# 4.net
KiCad netlist of a schematic drawn in EAGLE
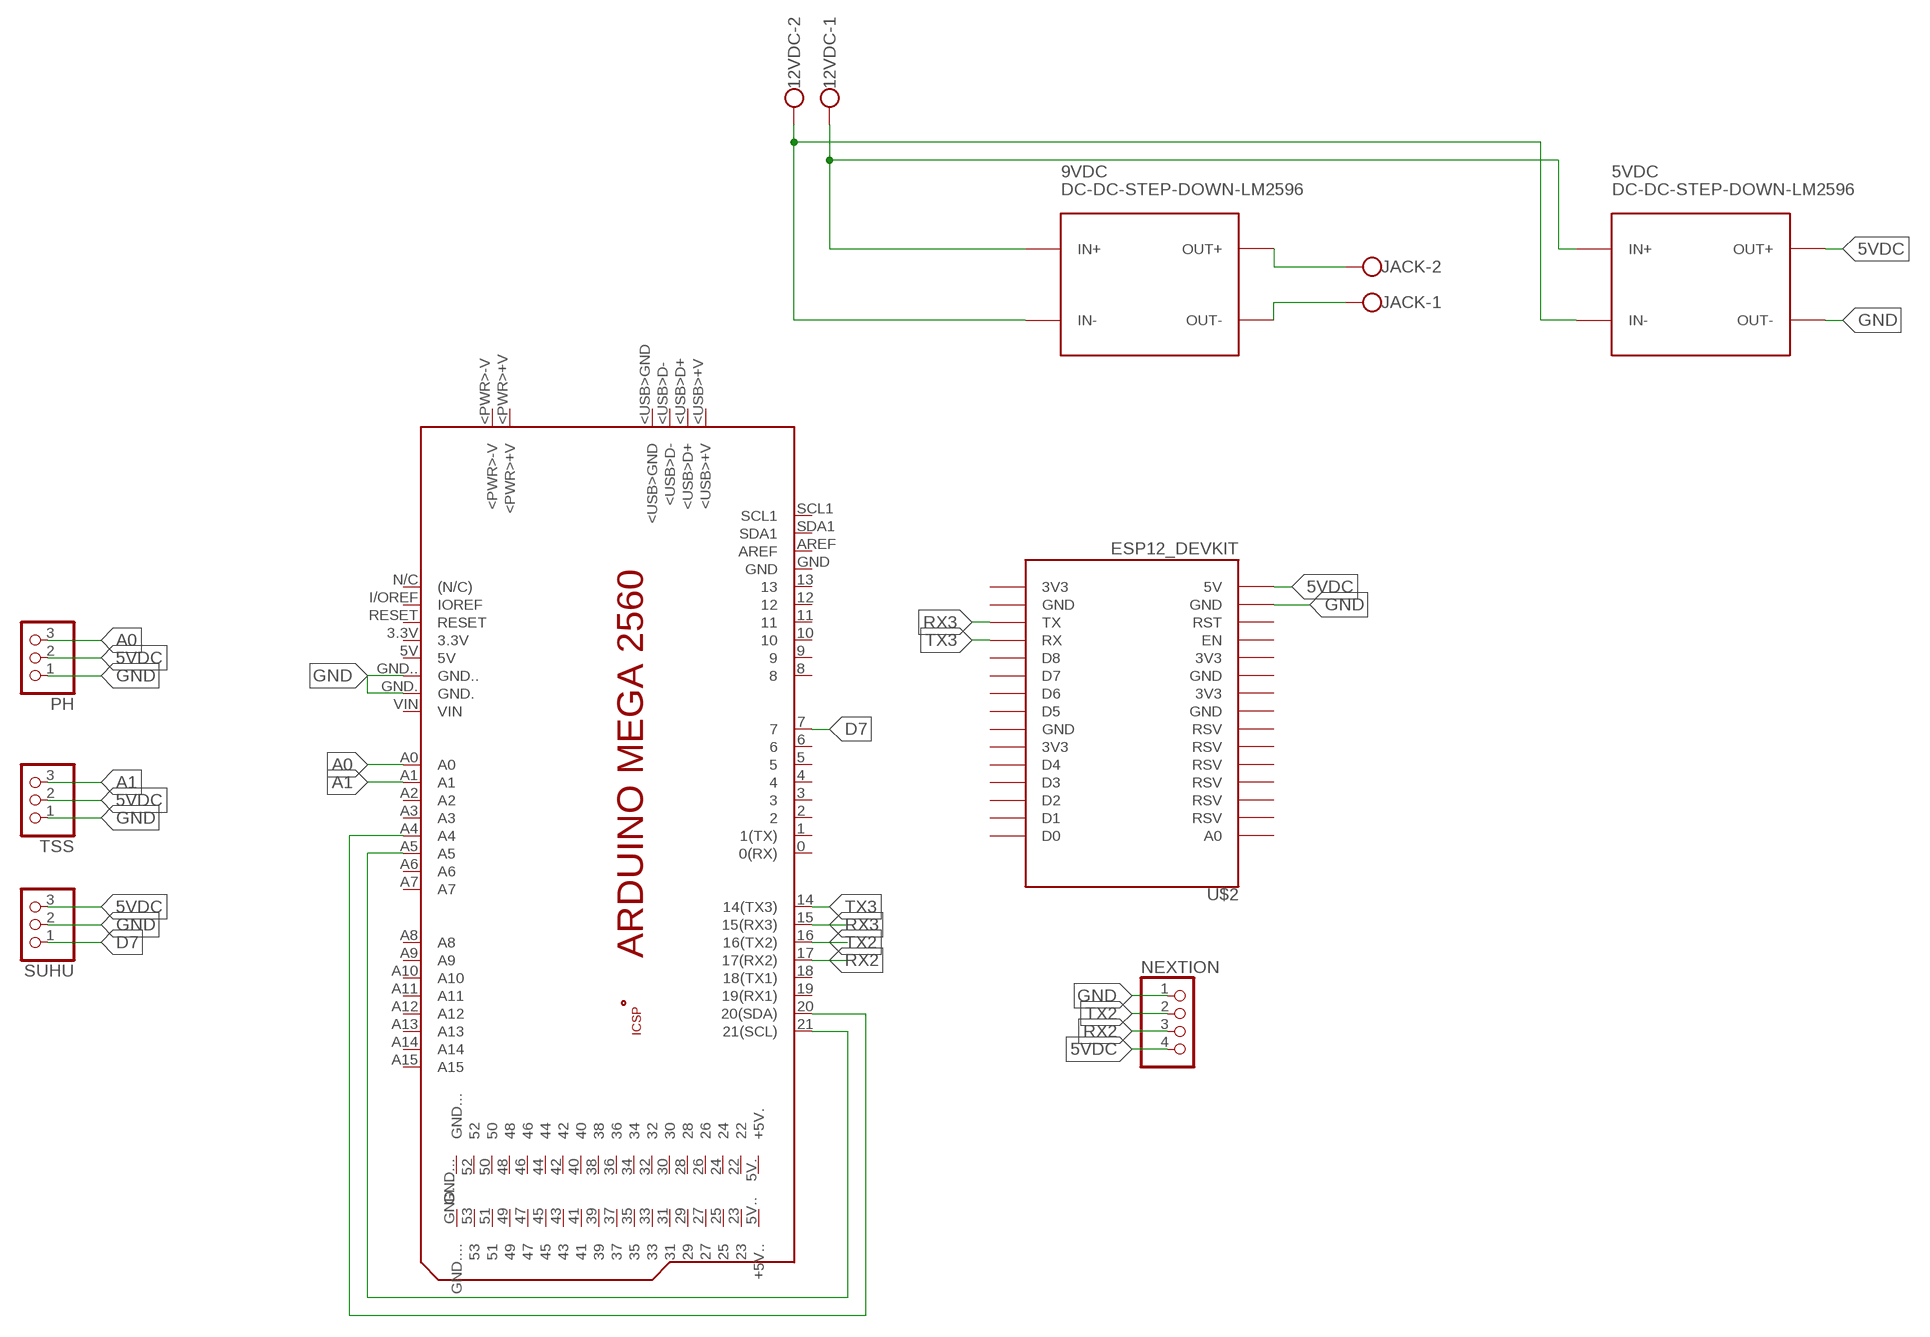
[diagram p0: schematic, sheet 1]

(export (version "E")
  (design (tool "Eeschema 10.0.6"))
  (components
    (comp (ref "5VDC")
      (value "DC-DC-STEP-DOWN-LM2596")
      (footprint "eagle-import:DC-DC-STEP-DOWN-LM2596")
      (libsource (lib "eagle-import") (part "DC-DC-STEP-DOWN-LM2596"))
    )
    (comp (ref "9VDC")
      (value "DC-DC-STEP-DOWN-LM2596")
      (footprint "eagle-import:DC-DC-STEP-DOWN-LM2596")
      (libsource (lib "eagle-import") (part "DC-DC-STEP-DOWN-LM2596"))
    )
    (comp (ref "12VDC")
      (value "W237-102")
      (footprint "eagle-import:W237-102")
      (fields (field (name "MPN") "237-102"))
      (libsource (lib "eagle-import") (part "W237-102"))
    )
    (comp (ref "JACK")
      (value "W237-102")
      (footprint "eagle-import:W237-102")
      (fields (field (name "MPN") "237-102"))
      (libsource (lib "eagle-import") (part "W237-102"))
    )
    (comp (ref "NEXTION")
      (value "PINHD-1X4")
      (footprint "eagle-import:1X04")
      (libsource (lib "eagle-import") (part "PINHD-1X4"))
    )
    (comp (ref "PCB1")
      (value "ARDUINO_MEGA2560")
      (footprint "eagle-import:ARDUINO_MEGA2560")
      (libsource (lib "eagle-import") (part "ARDUINO_MEGA2560"))
    )
    (comp (ref "PH")
      (value "PINHD-1X3")
      (footprint "eagle-import:1X03")
      (libsource (lib "eagle-import") (part "PINHD-1X3"))
    )
    (comp (ref "SUHU")
      (value "PINHD-1X3")
      (footprint "eagle-import:1X03")
      (libsource (lib "eagle-import") (part "PINHD-1X3"))
    )
    (comp (ref "TSS")
      (value "PINHD-1X3")
      (footprint "eagle-import:1X03")
      (libsource (lib "eagle-import") (part "PINHD-1X3"))
    )
    (comp (ref "U$2")
      (value "ESP12_DEVKIT")
      (footprint "eagle-import:ESP12_DEVKIT")
      (libsource (lib "eagle-import") (part "ESP12_DEVKIT"))
    )
  )
  (nets
    (net (code "1") (name "5VDC") (class "Default")
      (node (ref "5VDC") (pin "OUT+") (pinfunction "OUT+_OUT+") (pintype "bidirectional"))
      (node (ref "NEXTION") (pin "4") (pinfunction "4_4") (pintype "passive"))
      (node (ref "PH") (pin "2") (pinfunction "2_2") (pintype "passive"))
      (node (ref "SUHU") (pin "3") (pinfunction "3_3") (pintype "passive"))
      (node (ref "TSS") (pin "2") (pinfunction "2_2") (pintype "passive"))
      (node (ref "U$2") (pin "5V") (pinfunction "5V_5V") (pintype "bidirectional"))
    )
    (net (code "2") (name "A0") (class "Default")
      (node (ref "PCB1") (pin "A0") (pinfunction "A0_A0") (pintype "bidirectional"))
      (node (ref "PH") (pin "3") (pinfunction "3_3") (pintype "passive"))
    )
    (net (code "3") (name "A1") (class "Default")
      (node (ref "PCB1") (pin "A1") (pinfunction "A1_A1") (pintype "bidirectional"))
      (node (ref "TSS") (pin "3") (pinfunction "3_3") (pintype "passive"))
    )
    (net (code "4") (name "D7") (class "Default")
      (node (ref "PCB1") (pin "7") (pinfunction "7_7") (pintype "bidirectional"))
      (node (ref "SUHU") (pin "1") (pinfunction "1_1") (pintype "passive"))
    )
    (net (code "5") (name "GND") (class "Default")
      (node (ref "5VDC") (pin "OUT-") (pinfunction "OUT-_OUT-") (pintype "bidirectional"))
      (node (ref "NEXTION") (pin "1") (pinfunction "1_1") (pintype "passive"))
      (node (ref "PCB1") (pin "GND.") (pinfunction "GND._GND.") (pintype "bidirectional"))
      (node (ref "PCB1") (pin "GND..") (pinfunction "GND.._GND..") (pintype "bidirectional"))
      (node (ref "PH") (pin "1") (pinfunction "1_1") (pintype "passive"))
      (node (ref "SUHU") (pin "2") (pinfunction "2_2") (pintype "passive"))
      (node (ref "TSS") (pin "1") (pinfunction "1_1") (pintype "passive"))
      (node (ref "U$2") (pin "GND@1") (pinfunction "GND_GND@1") (pintype "bidirectional"))
    )
    (net (code "6") (name "Net-(12VDCA-KL)") (class "Default")
      (node (ref "12VDC") (pin "1") (pinfunction "KL_1") (pintype "passive"))
      (node (ref "5VDC") (pin "IN+") (pinfunction "IN+_IN+") (pintype "bidirectional"))
      (node (ref "9VDC") (pin "IN+") (pinfunction "IN+_IN+") (pintype "bidirectional"))
    )
    (net (code "7") (name "Net-(12VDCB-KL)") (class "Default")
      (node (ref "12VDC") (pin "2") (pinfunction "KL_2") (pintype "passive"))
      (node (ref "5VDC") (pin "IN-") (pinfunction "IN-_IN-") (pintype "bidirectional"))
      (node (ref "9VDC") (pin "IN-") (pinfunction "IN-_IN-") (pintype "bidirectional"))
    )
    (net (code "8") (name "Net-(JACKA-KL)") (class "Default")
      (node (ref "9VDC") (pin "OUT-") (pinfunction "OUT-_OUT-") (pintype "bidirectional"))
      (node (ref "JACK") (pin "1") (pinfunction "KL_1") (pintype "passive"))
    )
    (net (code "9") (name "Net-(JACKB-KL)") (class "Default")
      (node (ref "9VDC") (pin "OUT+") (pinfunction "OUT+_OUT+") (pintype "bidirectional"))
      (node (ref "JACK") (pin "2") (pinfunction "KL_2") (pintype "passive"))
    )
    (net (code "10") (name "Net-(PCB1-20(SDA))") (class "Default")
      (node (ref "PCB1") (pin "20") (pinfunction "20(SDA)_20") (pintype "bidirectional"))
      (node (ref "PCB1") (pin "A4") (pinfunction "A4_A4") (pintype "bidirectional"))
    )
    (net (code "11") (name "Net-(PCB1-21(SCL))") (class "Default")
      (node (ref "PCB1") (pin "21") (pinfunction "21(SCL)_21") (pintype "bidirectional"))
      (node (ref "PCB1") (pin "A5") (pinfunction "A5_A5") (pintype "bidirectional"))
    )
    (net (code "12") (name "RX2") (class "Default")
      (node (ref "NEXTION") (pin "3") (pinfunction "3_3") (pintype "passive"))
      (node (ref "PCB1") (pin "17") (pinfunction "17(RX2)_17") (pintype "bidirectional"))
    )
    (net (code "13") (name "RX3") (class "Default")
      (node (ref "PCB1") (pin "15") (pinfunction "15(RX3)_15") (pintype "bidirectional"))
      (node (ref "U$2") (pin "TX") (pinfunction "TX_TX") (pintype "bidirectional"))
    )
    (net (code "14") (name "TX2") (class "Default")
      (node (ref "NEXTION") (pin "2") (pinfunction "2_2") (pintype "passive"))
      (node (ref "PCB1") (pin "16") (pinfunction "16(TX2)_16") (pintype "bidirectional"))
    )
    (net (code "15") (name "TX3") (class "Default")
      (node (ref "PCB1") (pin "14") (pinfunction "14(TX3)_14") (pintype "bidirectional"))
      (node (ref "U$2") (pin "RX") (pinfunction "RX_RX") (pintype "bidirectional"))
    )
    (net (code "16") (name "unconnected-(PCB1-(N{slash}C)-PadN{slash}C)") (class "Default")
      (node (ref "PCB1") (pin "N/C") (pinfunction "(N/C)_N/C") (pintype "bidirectional"))
    )
    (net (code "17") (name "unconnected-(PCB1-+5V.-Pad5V.)") (class "Default")
      (node (ref "PCB1") (pin "5V.") (pinfunction "+5V._5V.") (pintype "bidirectional"))
    )
    (net (code "18") (name "unconnected-(PCB1-+5V..-Pad5V..)") (class "Default")
      (node (ref "PCB1") (pin "5V..") (pinfunction "+5V.._5V..") (pintype "bidirectional"))
    )
    (net (code "19") (name "unconnected-(PCB1-0(RX)-Pad0)") (class "Default")
      (node (ref "PCB1") (pin "0") (pinfunction "0(RX)_0") (pintype "bidirectional"))
    )
    (net (code "20") (name "unconnected-(PCB1-1(TX)-Pad1)") (class "Default")
      (node (ref "PCB1") (pin "1") (pinfunction "1(TX)_1") (pintype "bidirectional"))
    )
    (net (code "21") (name "unconnected-(PCB1-18(TX1)-Pad18)") (class "Default")
      (node (ref "PCB1") (pin "18") (pinfunction "18(TX1)_18") (pintype "bidirectional"))
    )
    (net (code "22") (name "unconnected-(PCB1-19(RX1)-Pad19)") (class "Default")
      (node (ref "PCB1") (pin "19") (pinfunction "19(RX1)_19") (pintype "bidirectional"))
    )
    (net (code "23") (name "unconnected-(PCB1-IOREF-PadI{slash}OREF)") (class "Default")
      (node (ref "PCB1") (pin "I/OREF") (pinfunction "IOREF_I/OREF") (pintype "bidirectional"))
    )
    (net (code "24") (name "unconnected-(PCB1-Pad+5V_)") (class "Default")
      (node (ref "PCB1") (pin "+5V_") (pinfunction "+5V__+5V_") (pintype "bidirectional"))
    )
    (net (code "25") (name "unconnected-(PCB1-Pad2)") (class "Default")
      (node (ref "PCB1") (pin "2") (pinfunction "2_2") (pintype "bidirectional"))
    )
    (net (code "26") (name "unconnected-(PCB1-Pad3)") (class "Default")
      (node (ref "PCB1") (pin "3") (pinfunction "3_3") (pintype "bidirectional"))
    )
    (net (code "27") (name "unconnected-(PCB1-Pad3.3V)") (class "Default")
      (node (ref "PCB1") (pin "3.3V") (pinfunction "3.3V_3.3V") (pintype "bidirectional"))
    )
    (net (code "28") (name "unconnected-(PCB1-Pad4)") (class "Default")
      (node (ref "PCB1") (pin "4") (pinfunction "4_4") (pintype "bidirectional"))
    )
    (net (code "29") (name "unconnected-(PCB1-Pad5)") (class "Default")
      (node (ref "PCB1") (pin "5") (pinfunction "5_5") (pintype "bidirectional"))
    )
    (net (code "30") (name "unconnected-(PCB1-Pad5V)") (class "Default")
      (node (ref "PCB1") (pin "5V") (pinfunction "5V_5V") (pintype "bidirectional"))
    )
    (net (code "31") (name "unconnected-(PCB1-Pad6)") (class "Default")
      (node (ref "PCB1") (pin "6") (pinfunction "6_6") (pintype "bidirectional"))
    )
    (net (code "32") (name "unconnected-(PCB1-Pad8)") (class "Default")
      (node (ref "PCB1") (pin "8") (pinfunction "8_8") (pintype "bidirectional"))
    )
    (net (code "33") (name "unconnected-(PCB1-Pad9)") (class "Default")
      (node (ref "PCB1") (pin "9") (pinfunction "9_9") (pintype "bidirectional"))
    )
    (net (code "34") (name "unconnected-(PCB1-Pad10)") (class "Default")
      (node (ref "PCB1") (pin "10") (pinfunction "10_10") (pintype "bidirectional"))
    )
    (net (code "35") (name "unconnected-(PCB1-Pad11)") (class "Default")
      (node (ref "PCB1") (pin "11") (pinfunction "11_11") (pintype "bidirectional"))
    )
    (net (code "36") (name "unconnected-(PCB1-Pad12)") (class "Default")
      (node (ref "PCB1") (pin "12") (pinfunction "12_12") (pintype "bidirectional"))
    )
    (net (code "37") (name "unconnected-(PCB1-Pad13)") (class "Default")
      (node (ref "PCB1") (pin "13") (pinfunction "13_13") (pintype "bidirectional"))
    )
    (net (code "38") (name "unconnected-(PCB1-Pad22)") (class "Default")
      (node (ref "PCB1") (pin "22") (pinfunction "22_22") (pintype "bidirectional"))
    )
    (net (code "39") (name "unconnected-(PCB1-Pad23)") (class "Default")
      (node (ref "PCB1") (pin "23") (pinfunction "23_23") (pintype "bidirectional"))
    )
    (net (code "40") (name "unconnected-(PCB1-Pad24)") (class "Default")
      (node (ref "PCB1") (pin "24") (pinfunction "24_24") (pintype "bidirectional"))
    )
    (net (code "41") (name "unconnected-(PCB1-Pad25)") (class "Default")
      (node (ref "PCB1") (pin "25") (pinfunction "25_25") (pintype "bidirectional"))
    )
    (net (code "42") (name "unconnected-(PCB1-Pad26)") (class "Default")
      (node (ref "PCB1") (pin "26") (pinfunction "26_26") (pintype "bidirectional"))
    )
    (net (code "43") (name "unconnected-(PCB1-Pad27)") (class "Default")
      (node (ref "PCB1") (pin "27") (pinfunction "27_27") (pintype "bidirectional"))
    )
    (net (code "44") (name "unconnected-(PCB1-Pad28)") (class "Default")
      (node (ref "PCB1") (pin "28") (pinfunction "28_28") (pintype "bidirectional"))
    )
    (net (code "45") (name "unconnected-(PCB1-Pad29)") (class "Default")
      (node (ref "PCB1") (pin "29") (pinfunction "29_29") (pintype "bidirectional"))
    )
    (net (code "46") (name "unconnected-(PCB1-Pad30)") (class "Default")
      (node (ref "PCB1") (pin "30") (pinfunction "30_30") (pintype "bidirectional"))
    )
    (net (code "47") (name "unconnected-(PCB1-Pad31)") (class "Default")
      (node (ref "PCB1") (pin "31") (pinfunction "31_31") (pintype "bidirectional"))
    )
    (net (code "48") (name "unconnected-(PCB1-Pad32)") (class "Default")
      (node (ref "PCB1") (pin "32") (pinfunction "32_32") (pintype "bidirectional"))
    )
    (net (code "49") (name "unconnected-(PCB1-Pad33)") (class "Default")
      (node (ref "PCB1") (pin "33") (pinfunction "33_33") (pintype "bidirectional"))
    )
    (net (code "50") (name "unconnected-(PCB1-Pad34)") (class "Default")
      (node (ref "PCB1") (pin "34") (pinfunction "34_34") (pintype "bidirectional"))
    )
    (net (code "51") (name "unconnected-(PCB1-Pad35)") (class "Default")
      (node (ref "PCB1") (pin "35") (pinfunction "35_35") (pintype "bidirectional"))
    )
    (net (code "52") (name "unconnected-(PCB1-Pad36)") (class "Default")
      (node (ref "PCB1") (pin "36") (pinfunction "36_36") (pintype "bidirectional"))
    )
    (net (code "53") (name "unconnected-(PCB1-Pad37)") (class "Default")
      (node (ref "PCB1") (pin "37") (pinfunction "37_37") (pintype "bidirectional"))
    )
    (net (code "54") (name "unconnected-(PCB1-Pad38)") (class "Default")
      (node (ref "PCB1") (pin "38") (pinfunction "38_38") (pintype "bidirectional"))
    )
    (net (code "55") (name "unconnected-(PCB1-Pad39)") (class "Default")
      (node (ref "PCB1") (pin "39") (pinfunction "39_39") (pintype "bidirectional"))
    )
    (net (code "56") (name "unconnected-(PCB1-Pad40)") (class "Default")
      (node (ref "PCB1") (pin "40") (pinfunction "40_40") (pintype "bidirectional"))
    )
    (net (code "57") (name "unconnected-(PCB1-Pad41)") (class "Default")
      (node (ref "PCB1") (pin "41") (pinfunction "41_41") (pintype "bidirectional"))
    )
    (net (code "58") (name "unconnected-(PCB1-Pad42)") (class "Default")
      (node (ref "PCB1") (pin "42") (pinfunction "42_42") (pintype "bidirectional"))
    )
    (net (code "59") (name "unconnected-(PCB1-Pad43)") (class "Default")
      (node (ref "PCB1") (pin "43") (pinfunction "43_43") (pintype "bidirectional"))
    )
    (net (code "60") (name "unconnected-(PCB1-Pad44)") (class "Default")
      (node (ref "PCB1") (pin "44") (pinfunction "44_44") (pintype "bidirectional"))
    )
    (net (code "61") (name "unconnected-(PCB1-Pad45)") (class "Default")
      (node (ref "PCB1") (pin "45") (pinfunction "45_45") (pintype "bidirectional"))
    )
    (net (code "62") (name "unconnected-(PCB1-Pad46)") (class "Default")
      (node (ref "PCB1") (pin "46") (pinfunction "46_46") (pintype "bidirectional"))
    )
    (net (code "63") (name "unconnected-(PCB1-Pad47)") (class "Default")
      (node (ref "PCB1") (pin "47") (pinfunction "47_47") (pintype "bidirectional"))
    )
    (net (code "64") (name "unconnected-(PCB1-Pad48)") (class "Default")
      (node (ref "PCB1") (pin "48") (pinfunction "48_48") (pintype "bidirectional"))
    )
    (net (code "65") (name "unconnected-(PCB1-Pad49)") (class "Default")
      (node (ref "PCB1") (pin "49") (pinfunction "49_49") (pintype "bidirectional"))
    )
    (net (code "66") (name "unconnected-(PCB1-Pad50)") (class "Default")
      (node (ref "PCB1") (pin "50") (pinfunction "50_50") (pintype "bidirectional"))
    )
    (net (code "67") (name "unconnected-(PCB1-Pad51)") (class "Default")
      (node (ref "PCB1") (pin "51") (pinfunction "51_51") (pintype "bidirectional"))
    )
    (net (code "68") (name "unconnected-(PCB1-Pad52)") (class "Default")
      (node (ref "PCB1") (pin "52") (pinfunction "52_52") (pintype "bidirectional"))
    )
    (net (code "69") (name "unconnected-(PCB1-Pad53)") (class "Default")
      (node (ref "PCB1") (pin "53") (pinfunction "53_53") (pintype "bidirectional"))
    )
    (net (code "70") (name "unconnected-(PCB1-Pad<PWR>+V)") (class "Default")
      (node (ref "PCB1") (pin "<PWR>+V") (pinfunction "<PWR>+V_<PWR>+V") (pintype "no_connect"))
    )
    (net (code "71") (name "unconnected-(PCB1-Pad<PWR>-V)") (class "Default")
      (node (ref "PCB1") (pin "<PWR>-V") (pinfunction "<PWR>-V_<PWR>-V") (pintype "no_connect"))
    )
    (net (code "72") (name "unconnected-(PCB1-Pad<USB>+V)") (class "Default")
      (node (ref "PCB1") (pin "<USB>+V") (pinfunction "<USB>+V_<USB>+V") (pintype "no_connect"))
    )
    (net (code "73") (name "unconnected-(PCB1-Pad<USB>D+)") (class "Default")
      (node (ref "PCB1") (pin "<USB>D+") (pinfunction "<USB>D+_<USB>D+") (pintype "no_connect"))
    )
    (net (code "74") (name "unconnected-(PCB1-Pad<USB>D-)") (class "Default")
      (node (ref "PCB1") (pin "<USB>D-") (pinfunction "<USB>D-_<USB>D-") (pintype "no_connect"))
    )
    (net (code "75") (name "unconnected-(PCB1-Pad<USB>GND)") (class "Default")
      (node (ref "PCB1") (pin "<USB>GND") (pinfunction "<USB>GND_<USB>GND") (pintype "no_connect"))
    )
    (net (code "76") (name "unconnected-(PCB1-PadA2)") (class "Default")
      (node (ref "PCB1") (pin "A2") (pinfunction "A2_A2") (pintype "bidirectional"))
    )
    (net (code "77") (name "unconnected-(PCB1-PadA3)") (class "Default")
      (node (ref "PCB1") (pin "A3") (pinfunction "A3_A3") (pintype "bidirectional"))
    )
    (net (code "78") (name "unconnected-(PCB1-PadA6)") (class "Default")
      (node (ref "PCB1") (pin "A6") (pinfunction "A6_A6") (pintype "bidirectional"))
    )
    (net (code "79") (name "unconnected-(PCB1-PadA7)") (class "Default")
      (node (ref "PCB1") (pin "A7") (pinfunction "A7_A7") (pintype "bidirectional"))
    )
    (net (code "80") (name "unconnected-(PCB1-PadA8)") (class "Default")
      (node (ref "PCB1") (pin "A8") (pinfunction "A8_A8") (pintype "bidirectional"))
    )
    (net (code "81") (name "unconnected-(PCB1-PadA9)") (class "Default")
      (node (ref "PCB1") (pin "A9") (pinfunction "A9_A9") (pintype "bidirectional"))
    )
    (net (code "82") (name "unconnected-(PCB1-PadA10)") (class "Default")
      (node (ref "PCB1") (pin "A10") (pinfunction "A10_A10") (pintype "bidirectional"))
    )
    (net (code "83") (name "unconnected-(PCB1-PadA11)") (class "Default")
      (node (ref "PCB1") (pin "A11") (pinfunction "A11_A11") (pintype "bidirectional"))
    )
    (net (code "84") (name "unconnected-(PCB1-PadA12)") (class "Default")
      (node (ref "PCB1") (pin "A12") (pinfunction "A12_A12") (pintype "bidirectional"))
    )
    (net (code "85") (name "unconnected-(PCB1-PadA13)") (class "Default")
      (node (ref "PCB1") (pin "A13") (pinfunction "A13_A13") (pintype "bidirectional"))
    )
    (net (code "86") (name "unconnected-(PCB1-PadA14)") (class "Default")
      (node (ref "PCB1") (pin "A14") (pinfunction "A14_A14") (pintype "bidirectional"))
    )
    (net (code "87") (name "unconnected-(PCB1-PadA15)") (class "Default")
      (node (ref "PCB1") (pin "A15") (pinfunction "A15_A15") (pintype "bidirectional"))
    )
    (net (code "88") (name "unconnected-(PCB1-PadAREF)") (class "Default")
      (node (ref "PCB1") (pin "AREF") (pinfunction "AREF_AREF") (pintype "bidirectional"))
    )
    (net (code "89") (name "unconnected-(PCB1-PadGND)") (class "Default")
      (node (ref "PCB1") (pin "GND") (pinfunction "GND_GND") (pintype "bidirectional"))
    )
    (net (code "90") (name "unconnected-(PCB1-PadGND...)") (class "Default")
      (node (ref "PCB1") (pin "GND...") (pinfunction "GND..._GND...") (pintype "bidirectional"))
    )
    (net (code "91") (name "unconnected-(PCB1-PadGND....)") (class "Default")
      (node (ref "PCB1") (pin "GND....") (pinfunction "GND...._GND....") (pintype "bidirectional"))
    )
    (net (code "92") (name "unconnected-(PCB1-PadGND__)") (class "Default")
      (node (ref "PCB1") (pin "GND__") (pinfunction "GND___GND__") (pintype "bidirectional"))
    )
    (net (code "93") (name "unconnected-(PCB1-PadMISO)") (class "Default")
      (node (ref "PCB1") (pin "MISO") (pinfunction "MISO_MISO") (pintype "bidirectional"))
    )
    (net (code "94") (name "unconnected-(PCB1-PadMOSI)") (class "Default")
      (node (ref "PCB1") (pin "MOSI") (pinfunction "MOSI_MOSI") (pintype "bidirectional"))
    )
    (net (code "95") (name "unconnected-(PCB1-PadRESET)") (class "Default")
      (node (ref "PCB1") (pin "RESET") (pinfunction "RESET_RESET") (pintype "bidirectional"))
    )
    (net (code "96") (name "unconnected-(PCB1-PadRESET.)") (class "Default")
      (node (ref "PCB1") (pin "RESET.") (pinfunction "RESET._RESET.") (pintype "bidirectional"))
    )
    (net (code "97") (name "unconnected-(PCB1-PadSCK)") (class "Default")
      (node (ref "PCB1") (pin "SCK") (pinfunction "SCK_SCK") (pintype "bidirectional"))
    )
    (net (code "98") (name "unconnected-(PCB1-PadSCL1)") (class "Default")
      (node (ref "PCB1") (pin "SCL1") (pinfunction "SCL1_SCL1") (pintype "bidirectional"))
    )
    (net (code "99") (name "unconnected-(PCB1-PadSDA1)") (class "Default")
      (node (ref "PCB1") (pin "SDA1") (pinfunction "SDA1_SDA1") (pintype "bidirectional"))
    )
    (net (code "100") (name "unconnected-(PCB1-PadVIN)") (class "Default")
      (node (ref "PCB1") (pin "VIN") (pinfunction "VIN_VIN") (pintype "bidirectional"))
    )
    (net (code "101") (name "unconnected-(U$2-3V3-Pad3V3@0)") (class "Default")
      (node (ref "U$2") (pin "3V3@0") (pinfunction "3V3_3V3@0") (pintype "bidirectional"))
    )
    (net (code "102") (name "unconnected-(U$2-3V3-Pad3V3@1)") (class "Default")
      (node (ref "U$2") (pin "3V3@1") (pinfunction "3V3_3V3@1") (pintype "bidirectional"))
    )
    (net (code "103") (name "unconnected-(U$2-3V3-Pad3V3@2)") (class "Default")
      (node (ref "U$2") (pin "3V3@2") (pinfunction "3V3_3V3@2") (pintype "bidirectional"))
    )
    (net (code "104") (name "unconnected-(U$2-3V3-Pad3V3@3)") (class "Default")
      (node (ref "U$2") (pin "3V3@3") (pinfunction "3V3_3V3@3") (pintype "bidirectional"))
    )
    (net (code "105") (name "unconnected-(U$2-GND-PadGND@0)") (class "Default")
      (node (ref "U$2") (pin "GND@0") (pinfunction "GND_GND@0") (pintype "bidirectional"))
    )
    (net (code "106") (name "unconnected-(U$2-GND-PadGND@2)") (class "Default")
      (node (ref "U$2") (pin "GND@2") (pinfunction "GND_GND@2") (pintype "bidirectional"))
    )
    (net (code "107") (name "unconnected-(U$2-GND-PadGND@3)") (class "Default")
      (node (ref "U$2") (pin "GND@3") (pinfunction "GND_GND@3") (pintype "bidirectional"))
    )
    (net (code "108") (name "unconnected-(U$2-GND-PadGND@4)") (class "Default")
      (node (ref "U$2") (pin "GND@4") (pinfunction "GND_GND@4") (pintype "bidirectional"))
    )
    (net (code "109") (name "unconnected-(U$2-PadA0)") (class "Default")
      (node (ref "U$2") (pin "A0") (pinfunction "A0_A0") (pintype "bidirectional"))
    )
    (net (code "110") (name "unconnected-(U$2-PadD0)") (class "Default")
      (node (ref "U$2") (pin "D0") (pinfunction "D0_D0") (pintype "bidirectional"))
    )
    (net (code "111") (name "unconnected-(U$2-PadD1)") (class "Default")
      (node (ref "U$2") (pin "D1") (pinfunction "D1_D1") (pintype "bidirectional"))
    )
    (net (code "112") (name "unconnected-(U$2-PadD2)") (class "Default")
      (node (ref "U$2") (pin "D2") (pinfunction "D2_D2") (pintype "bidirectional"))
    )
    (net (code "113") (name "unconnected-(U$2-PadD3)") (class "Default")
      (node (ref "U$2") (pin "D3") (pinfunction "D3_D3") (pintype "bidirectional"))
    )
    (net (code "114") (name "unconnected-(U$2-PadD4)") (class "Default")
      (node (ref "U$2") (pin "D4") (pinfunction "D4_D4") (pintype "bidirectional"))
    )
    (net (code "115") (name "unconnected-(U$2-PadD5)") (class "Default")
      (node (ref "U$2") (pin "D5") (pinfunction "D5_D5") (pintype "bidirectional"))
    )
    (net (code "116") (name "unconnected-(U$2-PadD6)") (class "Default")
      (node (ref "U$2") (pin "D6") (pinfunction "D6_D6") (pintype "bidirectional"))
    )
    (net (code "117") (name "unconnected-(U$2-PadD7)") (class "Default")
      (node (ref "U$2") (pin "D7") (pinfunction "D7_D7") (pintype "bidirectional"))
    )
    (net (code "118") (name "unconnected-(U$2-PadD8)") (class "Default")
      (node (ref "U$2") (pin "D8") (pinfunction "D8_D8") (pintype "bidirectional"))
    )
    (net (code "119") (name "unconnected-(U$2-PadEN)") (class "Default")
      (node (ref "U$2") (pin "EN") (pinfunction "EN_EN") (pintype "bidirectional"))
    )
    (net (code "120") (name "unconnected-(U$2-PadRST)") (class "Default")
      (node (ref "U$2") (pin "RST") (pinfunction "RST_RST") (pintype "bidirectional"))
    )
    (net (code "121") (name "unconnected-(U$2-RSV-PadRSV@0)") (class "Default")
      (node (ref "U$2") (pin "RSV@0") (pinfunction "RSV_RSV@0") (pintype "bidirectional"))
    )
    (net (code "122") (name "unconnected-(U$2-RSV-PadRSV@1)") (class "Default")
      (node (ref "U$2") (pin "RSV@1") (pinfunction "RSV_RSV@1") (pintype "bidirectional"))
    )
    (net (code "123") (name "unconnected-(U$2-RSV-PadRSV@2)") (class "Default")
      (node (ref "U$2") (pin "RSV@2") (pinfunction "RSV_RSV@2") (pintype "bidirectional"))
    )
    (net (code "124") (name "unconnected-(U$2-RSV-PadRSV@3)") (class "Default")
      (node (ref "U$2") (pin "RSV@3") (pinfunction "RSV_RSV@3") (pintype "bidirectional"))
    )
    (net (code "125") (name "unconnected-(U$2-RSV-PadRSV@4)") (class "Default")
      (node (ref "U$2") (pin "RSV@4") (pinfunction "RSV_RSV@4") (pintype "bidirectional"))
    )
    (net (code "126") (name "unconnected-(U$2-RSV-PadRSV@5)") (class "Default")
      (node (ref "U$2") (pin "RSV@5") (pinfunction "RSV_RSV@5") (pintype "bidirectional"))
    )
  )
)
